# Sheet2.net
KiCad netlist of a schematic drawn in Altium Designer
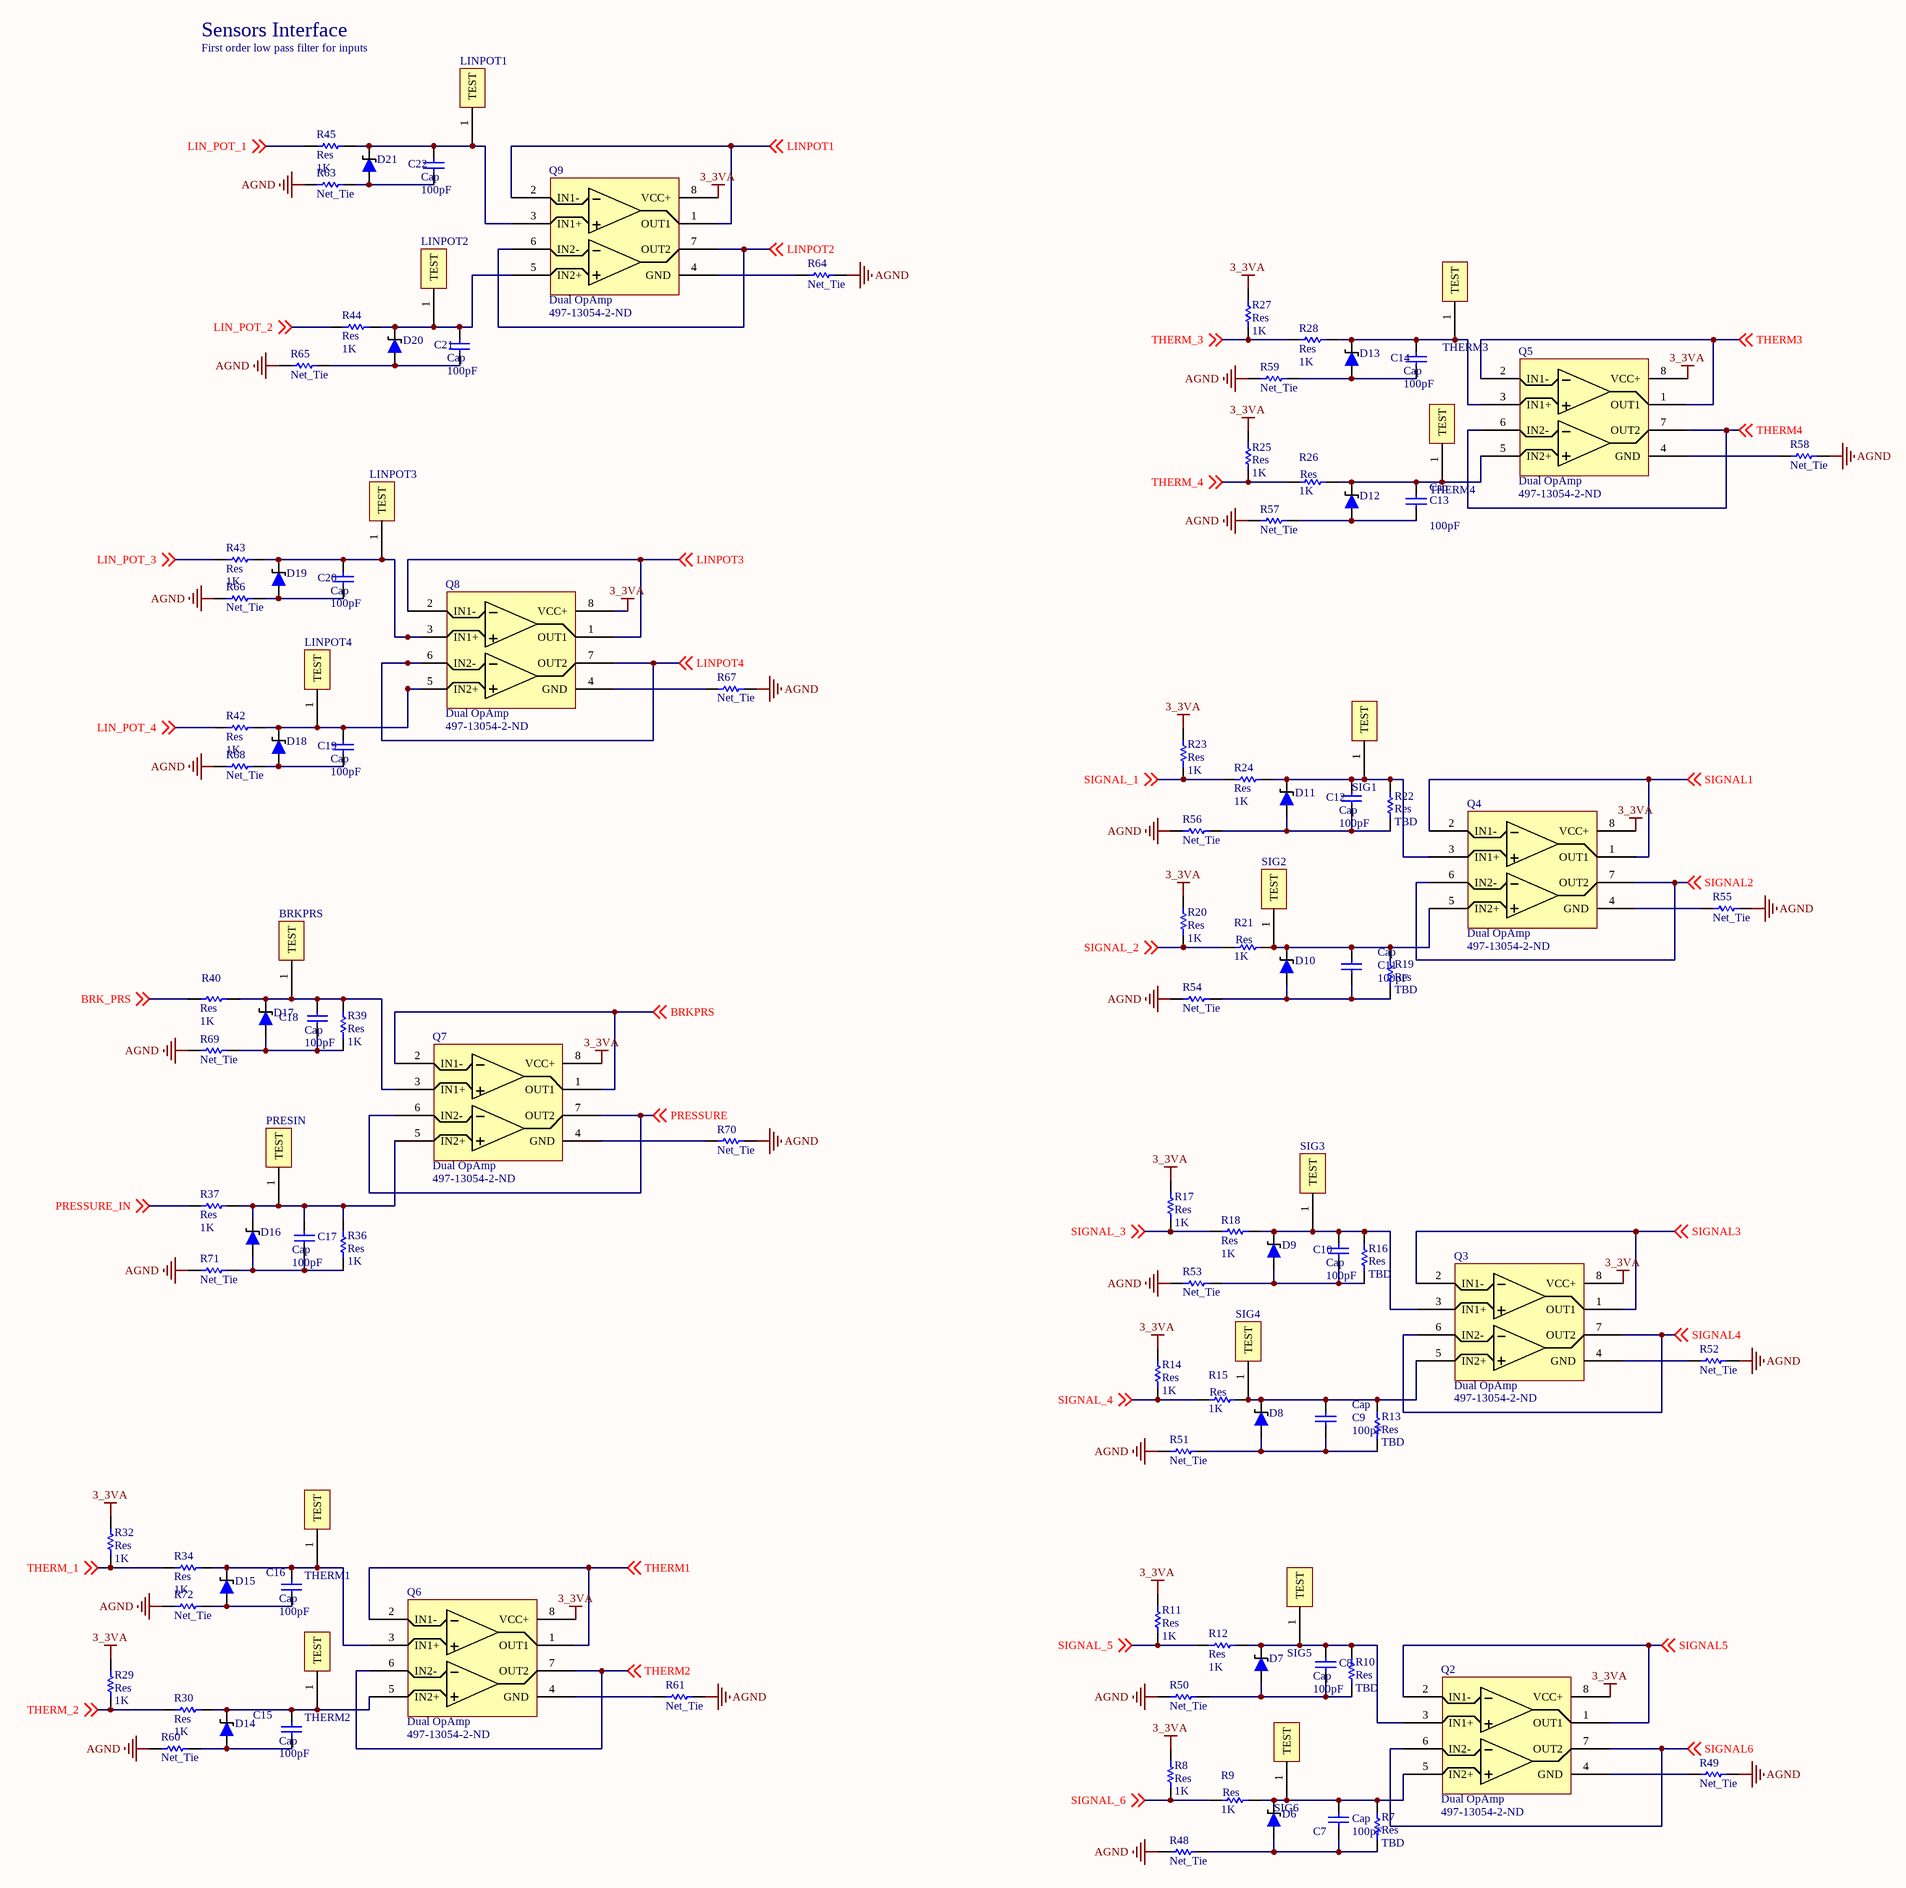
[diagram p0: Sheet2.SchDoc]

(export (version "E")
  (design (tool "Eeschema 10.0.6"))
  (components
    (comp (ref "C7")
      (value "Cap")
      (footprint "C0805")
      (description "Capacitor")
      (fields (field (name "ALTIUM_VALUE") "100pF") (field (name "PUBLISHER") "Altium Limited"))
      (libsource (lib "Capacitors") (part "Cap"))
    )
    (comp (ref "C8")
      (value "Cap")
      (footprint "C0805")
      (description "Capacitor")
      (fields (field (name "ALTIUM_VALUE") "100pF") (field (name "PUBLISHER") "Altium Limited"))
      (libsource (lib "Capacitors") (part "Cap"))
    )
    (comp (ref "C9")
      (value "Cap")
      (footprint "C0805")
      (description "Capacitor")
      (fields (field (name "ALTIUM_VALUE") "100pF") (field (name "PUBLISHER") "Altium Limited"))
      (libsource (lib "Capacitors") (part "Cap"))
    )
    (comp (ref "C10")
      (value "Cap")
      (footprint "C0805")
      (description "Capacitor")
      (fields (field (name "ALTIUM_VALUE") "100pF") (field (name "PUBLISHER") "Altium Limited"))
      (libsource (lib "Capacitors") (part "Cap"))
    )
    (comp (ref "C11")
      (value "Cap")
      (footprint "C0805")
      (description "Capacitor")
      (fields (field (name "ALTIUM_VALUE") "100pF") (field (name "PUBLISHER") "Altium Limited"))
      (libsource (lib "Capacitors") (part "Cap"))
    )
    (comp (ref "C12")
      (value "Cap")
      (footprint "C0805")
      (description "Capacitor")
      (fields (field (name "ALTIUM_VALUE") "100pF") (field (name "PUBLISHER") "Altium Limited"))
      (libsource (lib "Capacitors") (part "Cap"))
    )
    (comp (ref "C13")
      (value "Cap")
      (footprint "C0805")
      (description "Capacitor")
      (fields (field (name "ALTIUM_VALUE") "100pF") (field (name "PUBLISHER") "Altium Limited"))
      (libsource (lib "Capacitors") (part "Cap"))
    )
    (comp (ref "C14")
      (value "Cap")
      (footprint "C0805")
      (description "Capacitor")
      (fields (field (name "ALTIUM_VALUE") "100pF") (field (name "PUBLISHER") "Altium Limited"))
      (libsource (lib "Capacitors") (part "Cap"))
    )
    (comp (ref "C15")
      (value "Cap")
      (footprint "C0805")
      (description "Capacitor")
      (fields (field (name "ALTIUM_VALUE") "100pF") (field (name "PUBLISHER") "Altium Limited"))
      (libsource (lib "Capacitors") (part "Cap"))
    )
    (comp (ref "C16")
      (value "Cap")
      (footprint "C0805")
      (description "Capacitor")
      (fields (field (name "ALTIUM_VALUE") "100pF") (field (name "PUBLISHER") "Altium Limited"))
      (libsource (lib "Capacitors") (part "Cap"))
    )
    (comp (ref "C17")
      (value "Cap")
      (footprint "C0805")
      (description "Capacitor")
      (fields (field (name "ALTIUM_VALUE") "100pF") (field (name "PUBLISHER") "Altium Limited"))
      (libsource (lib "Capacitors") (part "Cap"))
    )
    (comp (ref "C18")
      (value "Cap")
      (footprint "C0805")
      (description "Capacitor")
      (fields (field (name "ALTIUM_VALUE") "100pF") (field (name "PUBLISHER") "Altium Limited"))
      (libsource (lib "Capacitors") (part "Cap"))
    )
    (comp (ref "C19")
      (value "Cap")
      (footprint "C0805")
      (description "Capacitor")
      (fields (field (name "ALTIUM_VALUE") "100pF") (field (name "PUBLISHER") "Altium Limited"))
      (libsource (lib "Capacitors") (part "Cap"))
    )
    (comp (ref "C20")
      (value "Cap")
      (footprint "C0805")
      (description "Capacitor")
      (fields (field (name "ALTIUM_VALUE") "100pF") (field (name "PUBLISHER") "Altium Limited"))
      (libsource (lib "Capacitors") (part "Cap"))
    )
    (comp (ref "C21")
      (value "Cap")
      (footprint "C0805")
      (description "Capacitor")
      (fields (field (name "ALTIUM_VALUE") "100pF") (field (name "PUBLISHER") "Altium Limited"))
      (libsource (lib "Capacitors") (part "Cap"))
    )
    (comp (ref "C22")
      (value "Cap")
      (footprint "C0805")
      (description "Capacitor")
      (fields (field (name "ALTIUM_VALUE") "100pF") (field (name "PUBLISHER") "Altium Limited"))
      (libsource (lib "Capacitors") (part "Cap"))
    )
    (comp (ref "D6")
      (value "MMSZ4684-TP")
      (footprint "MMSZ4684/9")
      (description "Zener Diode 3.3")
      (libsource (lib "DAU_Integrated_Library") (part "MMSZ4684-TP"))
    )
    (comp (ref "D7")
      (value "MMSZ4684-TP")
      (footprint "MMSZ4684/9")
      (description "Zener Diode 3.3")
      (libsource (lib "DAU_Integrated_Library") (part "MMSZ4684-TP"))
    )
    (comp (ref "D8")
      (value "MMSZ4684-TP")
      (footprint "MMSZ4684/9")
      (description "Zener Diode 3.3")
      (libsource (lib "DAU_Integrated_Library") (part "MMSZ4684-TP"))
    )
    (comp (ref "D9")
      (value "MMSZ4684-TP")
      (footprint "MMSZ4684/9")
      (description "Zener Diode 3.3")
      (libsource (lib "DAU_Integrated_Library") (part "MMSZ4684-TP"))
    )
    (comp (ref "D10")
      (value "MMSZ4684-TP")
      (footprint "MMSZ4684/9")
      (description "Zener Diode 3.3")
      (libsource (lib "DAU_Integrated_Library") (part "MMSZ4684-TP"))
    )
    (comp (ref "D11")
      (value "MMSZ4684-TP")
      (footprint "MMSZ4684/9")
      (description "Zener Diode 3.3")
      (libsource (lib "DAU_Integrated_Library") (part "MMSZ4684-TP"))
    )
    (comp (ref "D12")
      (value "MMSZ4684-TP")
      (footprint "MMSZ4684/9")
      (description "Zener Diode 3.3")
      (libsource (lib "DAU_Integrated_Library") (part "MMSZ4684-TP"))
    )
    (comp (ref "D13")
      (value "MMSZ4684-TP")
      (footprint "MMSZ4684/9")
      (description "Zener Diode 3.3")
      (libsource (lib "DAU_Integrated_Library") (part "MMSZ4684-TP"))
    )
    (comp (ref "D14")
      (value "MMSZ4684-TP")
      (footprint "MMSZ4684/9")
      (description "Zener Diode 3.3")
      (libsource (lib "DAU_Integrated_Library") (part "MMSZ4684-TP"))
    )
    (comp (ref "D15")
      (value "MMSZ4684-TP")
      (footprint "MMSZ4684/9")
      (description "Zener Diode 3.3")
      (libsource (lib "DAU_Integrated_Library") (part "MMSZ4684-TP"))
    )
    (comp (ref "D16")
      (value "MMSZ4689-TP")
      (footprint "MMSZ4684/9")
      (description "Zener Diode 5.1")
      (libsource (lib "DAU_Integrated_Library") (part "MMSZ4689-TP"))
    )
    (comp (ref "D17")
      (value "MMSZ4689-TP")
      (footprint "MMSZ4684/9")
      (description "Zener Diode 5.1")
      (libsource (lib "DAU_Integrated_Library") (part "MMSZ4689-TP"))
    )
    (comp (ref "D18")
      (value "MMSZ4684-TP")
      (footprint "MMSZ4684/9")
      (description "Zener Diode 3.3")
      (libsource (lib "DAU_Integrated_Library") (part "MMSZ4684-TP"))
    )
    (comp (ref "D19")
      (value "MMSZ4684-TP")
      (footprint "MMSZ4684/9")
      (description "Zener Diode 3.3")
      (libsource (lib "DAU_Integrated_Library") (part "MMSZ4684-TP"))
    )
    (comp (ref "D20")
      (value "MMSZ4684-TP")
      (footprint "MMSZ4684/9")
      (description "Zener Diode 3.3")
      (libsource (lib "DAU_Integrated_Library") (part "MMSZ4684-TP"))
    )
    (comp (ref "D21")
      (value "MMSZ4684-TP")
      (footprint "MMSZ4684/9")
      (description "Zener Diode 3.3")
      (libsource (lib "DAU_Integrated_Library") (part "MMSZ4684-TP"))
    )
    (comp (ref "Q2")
      (value "Dual OpAmp")
      (footprint "LMV358LIDT")
      (description "Standard Dual OpAmp")
      (fields (field (name "SUPPLIER PART NUMBER 1") "497-13054-2-ND"))
      (libsource (lib "DAU_Integrated_Library") (part "LMV358LIDT"))
    )
    (comp (ref "Q3")
      (value "Dual OpAmp")
      (footprint "LMV358LIDT")
      (description "Standard Dual OpAmp")
      (fields (field (name "SUPPLIER PART NUMBER 1") "497-13054-2-ND"))
      (libsource (lib "DAU_Integrated_Library") (part "LMV358LIDT"))
    )
    (comp (ref "Q4")
      (value "Dual OpAmp")
      (footprint "LMV358LIDT")
      (description "Standard Dual OpAmp")
      (fields (field (name "SUPPLIER PART NUMBER 1") "497-13054-2-ND"))
      (libsource (lib "DAU_Integrated_Library") (part "LMV358LIDT"))
    )
    (comp (ref "Q5")
      (value "Dual OpAmp")
      (footprint "LMV358LIDT")
      (description "Standard Dual OpAmp")
      (fields (field (name "SUPPLIER PART NUMBER 1") "497-13054-2-ND"))
      (libsource (lib "DAU_Integrated_Library") (part "LMV358LIDT"))
    )
    (comp (ref "Q6")
      (value "Dual OpAmp")
      (footprint "LMV358LIDT")
      (description "Standard Dual OpAmp")
      (fields (field (name "SUPPLIER PART NUMBER 1") "497-13054-2-ND"))
      (libsource (lib "DAU_Integrated_Library") (part "LMV358LIDT"))
    )
    (comp (ref "Q7")
      (value "Dual OpAmp")
      (footprint "LMV358LIDT")
      (description "Standard Dual OpAmp")
      (fields (field (name "SUPPLIER PART NUMBER 1") "497-13054-2-ND"))
      (libsource (lib "DAU_Integrated_Library") (part "LMV358LIDT"))
    )
    (comp (ref "Q8")
      (value "Dual OpAmp")
      (footprint "LMV358LIDT")
      (description "Standard Dual OpAmp")
      (fields (field (name "SUPPLIER PART NUMBER 1") "497-13054-2-ND"))
      (libsource (lib "DAU_Integrated_Library") (part "LMV358LIDT"))
    )
    (comp (ref "Q9")
      (value "Dual OpAmp")
      (footprint "LMV358LIDT")
      (description "Standard Dual OpAmp")
      (fields (field (name "SUPPLIER PART NUMBER 1") "497-13054-2-ND"))
      (libsource (lib "DAU_Integrated_Library") (part "LMV358LIDT"))
    )
    (comp (ref "R7")
      (value "Res")
      (footprint "2012[0805]")
      (description "Surface Mount Resistor")
      (fields (field (name "ALTIUM_VALUE") "TBD") (field (name "PUBLISHER") "Altium Limited"))
      (libsource (lib "Resistors") (part "Res"))
    )
    (comp (ref "R8")
      (value "Res")
      (footprint "2012[0805]")
      (description "Surface Mount Resistor")
      (fields (field (name "ALTIUM_VALUE") "1K") (field (name "PUBLISHER") "Altium Limited"))
      (libsource (lib "Resistors") (part "Res"))
    )
    (comp (ref "R9")
      (value "Res")
      (footprint "2012[0805]")
      (description "Surface Mount Resistor")
      (fields (field (name "ALTIUM_VALUE") "1K") (field (name "PUBLISHER") "Altium Limited"))
      (libsource (lib "Resistors") (part "Res"))
    )
    (comp (ref "R10")
      (value "Res")
      (footprint "2012[0805]")
      (description "Surface Mount Resistor")
      (fields (field (name "ALTIUM_VALUE") "TBD") (field (name "PUBLISHER") "Altium Limited"))
      (libsource (lib "Resistors") (part "Res"))
    )
    (comp (ref "R11")
      (value "Res")
      (footprint "2012[0805]")
      (description "Surface Mount Resistor")
      (fields (field (name "ALTIUM_VALUE") "1K") (field (name "PUBLISHER") "Altium Limited"))
      (libsource (lib "Resistors") (part "Res"))
    )
    (comp (ref "R12")
      (value "Res")
      (footprint "2012[0805]")
      (description "Surface Mount Resistor")
      (fields (field (name "ALTIUM_VALUE") "1K") (field (name "PUBLISHER") "Altium Limited"))
      (libsource (lib "Resistors") (part "Res"))
    )
    (comp (ref "R13")
      (value "Res")
      (footprint "2012[0805]")
      (description "Surface Mount Resistor")
      (fields (field (name "ALTIUM_VALUE") "TBD") (field (name "PUBLISHER") "Altium Limited"))
      (libsource (lib "Resistors") (part "Res"))
    )
    (comp (ref "R14")
      (value "Res")
      (footprint "2012[0805]")
      (description "Surface Mount Resistor")
      (fields (field (name "ALTIUM_VALUE") "1K") (field (name "PUBLISHER") "Altium Limited"))
      (libsource (lib "Resistors") (part "Res"))
    )
    (comp (ref "R15")
      (value "Res")
      (footprint "2012[0805]")
      (description "Surface Mount Resistor")
      (fields (field (name "ALTIUM_VALUE") "1K") (field (name "PUBLISHER") "Altium Limited"))
      (libsource (lib "Resistors") (part "Res"))
    )
    (comp (ref "R16")
      (value "Res")
      (footprint "2012[0805]")
      (description "Surface Mount Resistor")
      (fields (field (name "ALTIUM_VALUE") "TBD") (field (name "PUBLISHER") "Altium Limited"))
      (libsource (lib "Resistors") (part "Res"))
    )
    (comp (ref "R17")
      (value "Res")
      (footprint "2012[0805]")
      (description "Surface Mount Resistor")
      (fields (field (name "ALTIUM_VALUE") "1K") (field (name "PUBLISHER") "Altium Limited"))
      (libsource (lib "Resistors") (part "Res"))
    )
    (comp (ref "R18")
      (value "Res")
      (footprint "2012[0805]")
      (description "Surface Mount Resistor")
      (fields (field (name "ALTIUM_VALUE") "1K") (field (name "PUBLISHER") "Altium Limited"))
      (libsource (lib "Resistors") (part "Res"))
    )
    (comp (ref "R19")
      (value "Res")
      (footprint "2012[0805]")
      (description "Surface Mount Resistor")
      (fields (field (name "ALTIUM_VALUE") "TBD") (field (name "PUBLISHER") "Altium Limited"))
      (libsource (lib "Resistors") (part "Res"))
    )
    (comp (ref "R20")
      (value "Res")
      (footprint "2012[0805]")
      (description "Surface Mount Resistor")
      (fields (field (name "ALTIUM_VALUE") "1K") (field (name "PUBLISHER") "Altium Limited"))
      (libsource (lib "Resistors") (part "Res"))
    )
    (comp (ref "R21")
      (value "Res")
      (footprint "2012[0805]")
      (description "Surface Mount Resistor")
      (fields (field (name "ALTIUM_VALUE") "1K") (field (name "PUBLISHER") "Altium Limited"))
      (libsource (lib "Resistors") (part "Res"))
    )
    (comp (ref "R22")
      (value "Res")
      (footprint "2012[0805]")
      (description "Surface Mount Resistor")
      (fields (field (name "ALTIUM_VALUE") "TBD") (field (name "PUBLISHER") "Altium Limited"))
      (libsource (lib "Resistors") (part "Res"))
    )
    (comp (ref "R23")
      (value "Res")
      (footprint "2012[0805]")
      (description "Surface Mount Resistor")
      (fields (field (name "ALTIUM_VALUE") "1K") (field (name "PUBLISHER") "Altium Limited"))
      (libsource (lib "Resistors") (part "Res"))
    )
    (comp (ref "R24")
      (value "Res")
      (footprint "2012[0805]")
      (description "Surface Mount Resistor")
      (fields (field (name "ALTIUM_VALUE") "1K") (field (name "PUBLISHER") "Altium Limited"))
      (libsource (lib "Resistors") (part "Res"))
    )
    (comp (ref "R25")
      (value "Res")
      (footprint "2012[0805]")
      (description "Surface Mount Resistor")
      (fields (field (name "ALTIUM_VALUE") "1K") (field (name "PUBLISHER") "Altium Limited"))
      (libsource (lib "Resistors") (part "Res"))
    )
    (comp (ref "R26")
      (value "Res")
      (footprint "2012[0805]")
      (description "Surface Mount Resistor")
      (fields (field (name "ALTIUM_VALUE") "1K") (field (name "PUBLISHER") "Altium Limited"))
      (libsource (lib "Resistors") (part "Res"))
    )
    (comp (ref "R27")
      (value "Res")
      (footprint "2012[0805]")
      (description "Surface Mount Resistor")
      (fields (field (name "ALTIUM_VALUE") "1K") (field (name "PUBLISHER") "Altium Limited"))
      (libsource (lib "Resistors") (part "Res"))
    )
    (comp (ref "R28")
      (value "Res")
      (footprint "2012[0805]")
      (description "Surface Mount Resistor")
      (fields (field (name "ALTIUM_VALUE") "1K") (field (name "PUBLISHER") "Altium Limited"))
      (libsource (lib "Resistors") (part "Res"))
    )
    (comp (ref "R29")
      (value "Res")
      (footprint "2012[0805]")
      (description "Surface Mount Resistor")
      (fields (field (name "ALTIUM_VALUE") "1K") (field (name "PUBLISHER") "Altium Limited"))
      (libsource (lib "Resistors") (part "Res"))
    )
    (comp (ref "R30")
      (value "Res")
      (footprint "2012[0805]")
      (description "Surface Mount Resistor")
      (fields (field (name "ALTIUM_VALUE") "1K") (field (name "PUBLISHER") "Altium Limited"))
      (libsource (lib "Resistors") (part "Res"))
    )
    (comp (ref "R32")
      (value "Res")
      (footprint "2012[0805]")
      (description "Surface Mount Resistor")
      (fields (field (name "ALTIUM_VALUE") "1K") (field (name "PUBLISHER") "Altium Limited"))
      (libsource (lib "Resistors") (part "Res"))
    )
    (comp (ref "R34")
      (value "Res")
      (footprint "2012[0805]")
      (description "Surface Mount Resistor")
      (fields (field (name "ALTIUM_VALUE") "1K") (field (name "PUBLISHER") "Altium Limited"))
      (libsource (lib "Resistors") (part "Res"))
    )
    (comp (ref "R36")
      (value "Res")
      (footprint "2012[0805]")
      (description "Surface Mount Resistor")
      (fields (field (name "ALTIUM_VALUE") "1K") (field (name "PUBLISHER") "Altium Limited"))
      (libsource (lib "Resistors") (part "Res"))
    )
    (comp (ref "R37")
      (value "Res")
      (footprint "2012[0805]")
      (description "Surface Mount Resistor")
      (fields (field (name "ALTIUM_VALUE") "1K") (field (name "PUBLISHER") "Altium Limited"))
      (libsource (lib "Resistors") (part "Res"))
    )
    (comp (ref "R39")
      (value "Res")
      (footprint "2012[0805]")
      (description "Surface Mount Resistor")
      (fields (field (name "ALTIUM_VALUE") "1K") (field (name "PUBLISHER") "Altium Limited"))
      (libsource (lib "Resistors") (part "Res"))
    )
    (comp (ref "R40")
      (value "Res")
      (footprint "2012[0805]")
      (description "Surface Mount Resistor")
      (fields (field (name "ALTIUM_VALUE") "1K") (field (name "PUBLISHER") "Altium Limited"))
      (libsource (lib "Resistors") (part "Res"))
    )
    (comp (ref "R42")
      (value "Res")
      (footprint "2012[0805]")
      (description "Surface Mount Resistor")
      (fields (field (name "ALTIUM_VALUE") "1K") (field (name "PUBLISHER") "Altium Limited"))
      (libsource (lib "Resistors") (part "Res"))
    )
    (comp (ref "R43")
      (value "Res")
      (footprint "2012[0805]")
      (description "Surface Mount Resistor")
      (fields (field (name "ALTIUM_VALUE") "1K") (field (name "PUBLISHER") "Altium Limited"))
      (libsource (lib "Resistors") (part "Res"))
    )
    (comp (ref "R44")
      (value "Res")
      (footprint "2012[0805]")
      (description "Surface Mount Resistor")
      (fields (field (name "ALTIUM_VALUE") "1K") (field (name "PUBLISHER") "Altium Limited"))
      (libsource (lib "Resistors") (part "Res"))
    )
    (comp (ref "R45")
      (value "Res")
      (footprint "2012[0805]")
      (description "Surface Mount Resistor")
      (fields (field (name "ALTIUM_VALUE") "1K") (field (name "PUBLISHER") "Altium Limited"))
      (libsource (lib "Resistors") (part "Res"))
    )
    (comp (ref "R48")
      (value "Net_Tie")
      (footprint "NetTie 0805 10mil")
      (description "Surface Mount Resistor")
      (libsource (lib "Resistors") (part "Res_NetTie"))
    )
    (comp (ref "R49")
      (value "Net_Tie")
      (footprint "NetTie 0805 10mil")
      (description "Surface Mount Resistor")
      (libsource (lib "Resistors") (part "Res_NetTie"))
    )
    (comp (ref "R50")
      (value "Net_Tie")
      (footprint "NetTie 0805 10mil")
      (description "Surface Mount Resistor")
      (libsource (lib "Resistors") (part "Res_NetTie"))
    )
    (comp (ref "R51")
      (value "Net_Tie")
      (footprint "NetTie 0805 10mil")
      (description "Surface Mount Resistor")
      (libsource (lib "Resistors") (part "Res_NetTie"))
    )
    (comp (ref "R52")
      (value "Net_Tie")
      (footprint "NetTie 0805 10mil")
      (description "Surface Mount Resistor")
      (libsource (lib "Resistors") (part "Res_NetTie"))
    )
    (comp (ref "R53")
      (value "Net_Tie")
      (footprint "NetTie 0805 10mil")
      (description "Surface Mount Resistor")
      (libsource (lib "Resistors") (part "Res_NetTie"))
    )
    (comp (ref "R54")
      (value "Net_Tie")
      (footprint "NetTie 0805 10mil")
      (description "Surface Mount Resistor")
      (libsource (lib "Resistors") (part "Res_NetTie"))
    )
    (comp (ref "R55")
      (value "Net_Tie")
      (footprint "NetTie 0805 10mil")
      (description "Surface Mount Resistor")
      (libsource (lib "Resistors") (part "Res_NetTie"))
    )
    (comp (ref "R56")
      (value "Net_Tie")
      (footprint "NetTie 0805 10mil")
      (description "Surface Mount Resistor")
      (libsource (lib "Resistors") (part "Res_NetTie"))
    )
    (comp (ref "R57")
      (value "Net_Tie")
      (footprint "NetTie 0805 10mil")
      (description "Surface Mount Resistor")
      (libsource (lib "Resistors") (part "Res_NetTie"))
    )
    (comp (ref "R58")
      (value "Net_Tie")
      (footprint "NetTie 0805 10mil")
      (description "Surface Mount Resistor")
      (libsource (lib "Resistors") (part "Res_NetTie"))
    )
    (comp (ref "R59")
      (value "Net_Tie")
      (footprint "NetTie 0805 10mil")
      (description "Surface Mount Resistor")
      (libsource (lib "Resistors") (part "Res_NetTie"))
    )
    (comp (ref "R60")
      (value "Net_Tie")
      (footprint "NetTie 0805 10mil")
      (description "Surface Mount Resistor")
      (libsource (lib "Resistors") (part "Res_NetTie"))
    )
    (comp (ref "R61")
      (value "Net_Tie")
      (footprint "NetTie 0805 10mil")
      (description "Surface Mount Resistor")
      (libsource (lib "Resistors") (part "Res_NetTie"))
    )
    (comp (ref "R63")
      (value "Net_Tie")
      (footprint "NetTie 0805 10mil")
      (description "Surface Mount Resistor")
      (libsource (lib "Resistors") (part "Res_NetTie"))
    )
    (comp (ref "R64")
      (value "Net_Tie")
      (footprint "NetTie 0805 10mil")
      (description "Surface Mount Resistor")
      (libsource (lib "Resistors") (part "Res_NetTie"))
    )
    (comp (ref "R65")
      (value "Net_Tie")
      (footprint "NetTie 0805 10mil")
      (description "Surface Mount Resistor")
      (libsource (lib "Resistors") (part "Res_NetTie"))
    )
    (comp (ref "R66")
      (value "Net_Tie")
      (footprint "NetTie 0805 10mil")
      (description "Surface Mount Resistor")
      (libsource (lib "Resistors") (part "Res_NetTie"))
    )
    (comp (ref "R67")
      (value "Net_Tie")
      (footprint "NetTie 0805 10mil")
      (description "Surface Mount Resistor")
      (libsource (lib "Resistors") (part "Res_NetTie"))
    )
    (comp (ref "R68")
      (value "Net_Tie")
      (footprint "NetTie 0805 10mil")
      (description "Surface Mount Resistor")
      (libsource (lib "Resistors") (part "Res_NetTie"))
    )
    (comp (ref "R69")
      (value "Net_Tie")
      (footprint "NetTie 0805 10mil")
      (description "Surface Mount Resistor")
      (libsource (lib "Resistors") (part "Res_NetTie"))
    )
    (comp (ref "R70")
      (value "Net_Tie")
      (footprint "NetTie 0805 10mil")
      (description "Surface Mount Resistor")
      (libsource (lib "Resistors") (part "Res_NetTie"))
    )
    (comp (ref "R71")
      (value "Net_Tie")
      (footprint "NetTie 0805 10mil")
      (description "Surface Mount Resistor")
      (libsource (lib "Resistors") (part "Res_NetTie"))
    )
    (comp (ref "R72")
      (value "Net_Tie")
      (footprint "NetTie 0805 10mil")
      (description "Surface Mount Resistor")
      (libsource (lib "Resistors") (part "Res_NetTie"))
    )
    (comp (ref "TP1")
      (value "SIG6")
      (footprint "TEST POINT 5000K")
      (description "5000-5004, 5015-5019 Keystone Electronics")
      (libsource (lib "Mechanical_Devices") (part "Test Point"))
    )
    (comp (ref "TP2")
      (value "SIG5")
      (footprint "TEST POINT 5000K")
      (description "5000-5004, 5015-5019 Keystone Electronics")
      (libsource (lib "Mechanical_Devices") (part "Test Point"))
    )
    (comp (ref "TP3")
      (value "SIG4")
      (footprint "TEST POINT 5000K")
      (description "5000-5004, 5015-5019 Keystone Electronics")
      (libsource (lib "Mechanical_Devices") (part "Test Point"))
    )
    (comp (ref "TP4")
      (value "SIG3")
      (footprint "TEST POINT 5000K")
      (description "5000-5004, 5015-5019 Keystone Electronics")
      (libsource (lib "Mechanical_Devices") (part "Test Point"))
    )
    (comp (ref "TP5")
      (value "SIG2")
      (footprint "TEST POINT 5000K")
      (description "5000-5004, 5015-5019 Keystone Electronics")
      (libsource (lib "Mechanical_Devices") (part "Test Point"))
    )
    (comp (ref "TP6")
      (value "SIG1")
      (footprint "TEST POINT 5000K")
      (description "5000-5004, 5015-5019 Keystone Electronics")
      (libsource (lib "Mechanical_Devices") (part "Test Point"))
    )
    (comp (ref "TP7")
      (value "THERM4")
      (footprint "TEST POINT 5000K")
      (description "5000-5004, 5015-5019 Keystone Electronics")
      (libsource (lib "Mechanical_Devices") (part "Test Point"))
    )
    (comp (ref "TP8")
      (value "THERM3")
      (footprint "TEST POINT 5000K")
      (description "5000-5004, 5015-5019 Keystone Electronics")
      (libsource (lib "Mechanical_Devices") (part "Test Point"))
    )
    (comp (ref "TP9")
      (value "THERM2")
      (footprint "TEST POINT 5000K")
      (description "5000-5004, 5015-5019 Keystone Electronics")
      (libsource (lib "Mechanical_Devices") (part "Test Point"))
    )
    (comp (ref "TP10")
      (value "THERM1")
      (footprint "TEST POINT 5000K")
      (description "5000-5004, 5015-5019 Keystone Electronics")
      (libsource (lib "Mechanical_Devices") (part "Test Point"))
    )
    (comp (ref "TP11")
      (value "PRESIN")
      (footprint "TEST POINT 5000K")
      (description "5000-5004, 5015-5019 Keystone Electronics")
      (libsource (lib "Mechanical_Devices") (part "Test Point"))
    )
    (comp (ref "TP12")
      (value "BRKPRS")
      (footprint "TEST POINT 5000K")
      (description "5000-5004, 5015-5019 Keystone Electronics")
      (libsource (lib "Mechanical_Devices") (part "Test Point"))
    )
    (comp (ref "TP13")
      (value "LINPOT4")
      (footprint "TEST POINT 5000K")
      (description "5000-5004, 5015-5019 Keystone Electronics")
      (libsource (lib "Mechanical_Devices") (part "Test Point"))
    )
    (comp (ref "TP14")
      (value "LINPOT3")
      (footprint "TEST POINT 5000K")
      (description "5000-5004, 5015-5019 Keystone Electronics")
      (libsource (lib "Mechanical_Devices") (part "Test Point"))
    )
    (comp (ref "TP15")
      (value "LINPOT2")
      (footprint "TEST POINT 5000K")
      (description "5000-5004, 5015-5019 Keystone Electronics")
      (libsource (lib "Mechanical_Devices") (part "Test Point"))
    )
    (comp (ref "TP16")
      (value "LINPOT1")
      (footprint "TEST POINT 5000K")
      (description "5000-5004, 5015-5019 Keystone Electronics")
      (libsource (lib "Mechanical_Devices") (part "Test Point"))
    )
  )
  (nets
    (net (code "1") (name "3_3VA") (class "Default")
      (node (ref "Q2") (pin "8") (pinfunction "VCC+_8") (pintype "passive"))
      (node (ref "Q3") (pin "8") (pinfunction "VCC+_8") (pintype "passive"))
      (node (ref "Q4") (pin "8") (pinfunction "VCC+_8") (pintype "passive"))
      (node (ref "Q5") (pin "8") (pinfunction "VCC+_8") (pintype "passive"))
      (node (ref "Q6") (pin "8") (pinfunction "VCC+_8") (pintype "passive"))
      (node (ref "Q7") (pin "8") (pinfunction "VCC+_8") (pintype "passive"))
      (node (ref "Q8") (pin "8") (pinfunction "VCC+_8") (pintype "passive"))
      (node (ref "Q9") (pin "8") (pinfunction "VCC+_8") (pintype "passive"))
      (node (ref "R11") (pin "2") (pinfunction "2_2") (pintype "passive"))
      (node (ref "R14") (pin "2") (pinfunction "2_2") (pintype "passive"))
      (node (ref "R17") (pin "2") (pinfunction "2_2") (pintype "passive"))
      (node (ref "R20") (pin "2") (pinfunction "2_2") (pintype "passive"))
      (node (ref "R23") (pin "2") (pinfunction "2_2") (pintype "passive"))
      (node (ref "R25") (pin "2") (pinfunction "2_2") (pintype "passive"))
      (node (ref "R27") (pin "2") (pinfunction "2_2") (pintype "passive"))
      (node (ref "R29") (pin "2") (pinfunction "2_2") (pintype "passive"))
      (node (ref "R32") (pin "2") (pinfunction "2_2") (pintype "passive"))
      (node (ref "R8") (pin "2") (pinfunction "2_2") (pintype "passive"))
    )
    (net (code "2") (name "AGND") (class "Default")
      (node (ref "R48") (pin "2") (pinfunction "2_2") (pintype "passive"))
      (node (ref "R49") (pin "2") (pinfunction "2_2") (pintype "passive"))
      (node (ref "R50") (pin "2") (pinfunction "2_2") (pintype "passive"))
      (node (ref "R51") (pin "2") (pinfunction "2_2") (pintype "passive"))
      (node (ref "R52") (pin "2") (pinfunction "2_2") (pintype "passive"))
      (node (ref "R53") (pin "2") (pinfunction "2_2") (pintype "passive"))
      (node (ref "R54") (pin "2") (pinfunction "2_2") (pintype "passive"))
      (node (ref "R55") (pin "2") (pinfunction "2_2") (pintype "passive"))
      (node (ref "R56") (pin "2") (pinfunction "2_2") (pintype "passive"))
      (node (ref "R57") (pin "2") (pinfunction "2_2") (pintype "passive"))
      (node (ref "R58") (pin "2") (pinfunction "2_2") (pintype "passive"))
      (node (ref "R59") (pin "2") (pinfunction "2_2") (pintype "passive"))
      (node (ref "R60") (pin "2") (pinfunction "2_2") (pintype "passive"))
      (node (ref "R61") (pin "2") (pinfunction "2_2") (pintype "passive"))
      (node (ref "R63") (pin "1") (pinfunction "1_1") (pintype "passive"))
      (node (ref "R64") (pin "2") (pinfunction "2_2") (pintype "passive"))
      (node (ref "R65") (pin "1") (pinfunction "1_1") (pintype "passive"))
      (node (ref "R66") (pin "2") (pinfunction "2_2") (pintype "passive"))
      (node (ref "R67") (pin "2") (pinfunction "2_2") (pintype "passive"))
      (node (ref "R68") (pin "2") (pinfunction "2_2") (pintype "passive"))
      (node (ref "R69") (pin "2") (pinfunction "2_2") (pintype "passive"))
      (node (ref "R70") (pin "2") (pinfunction "2_2") (pintype "passive"))
      (node (ref "R71") (pin "2") (pinfunction "2_2") (pintype "passive"))
      (node (ref "R72") (pin "2") (pinfunction "2_2") (pintype "passive"))
    )
    (net (code "3") (name "BRKPRS") (class "Default")
      (node (ref "Q7") (pin "1") (pinfunction "OUT1_1") (pintype "passive"))
      (node (ref "Q7") (pin "2") (pinfunction "IN1-_2") (pintype "passive"))
    )
    (net (code "4") (name "BRK_PRS") (class "Default")
      (node (ref "R40") (pin "1") (pinfunction "1_1") (pintype "passive"))
    )
    (net (code "5") (name "LINPOT1") (class "Default")
      (node (ref "Q9") (pin "1") (pinfunction "OUT1_1") (pintype "passive"))
      (node (ref "Q9") (pin "2") (pinfunction "IN1-_2") (pintype "passive"))
    )
    (net (code "6") (name "LINPOT2") (class "Default")
      (node (ref "Q9") (pin "6") (pinfunction "IN2-_6") (pintype "passive"))
      (node (ref "Q9") (pin "7") (pinfunction "OUT2_7") (pintype "passive"))
    )
    (net (code "7") (name "LINPOT3") (class "Default")
      (node (ref "Q8") (pin "1") (pinfunction "OUT1_1") (pintype "passive"))
      (node (ref "Q8") (pin "2") (pinfunction "IN1-_2") (pintype "passive"))
    )
    (net (code "8") (name "LINPOT4") (class "Default")
      (node (ref "Q8") (pin "6") (pinfunction "IN2-_6") (pintype "passive"))
      (node (ref "Q8") (pin "7") (pinfunction "OUT2_7") (pintype "passive"))
    )
    (net (code "9") (name "LIN_POT_1") (class "Default")
      (node (ref "R45") (pin "1") (pinfunction "1_1") (pintype "passive"))
    )
    (net (code "10") (name "LIN_POT_2") (class "Default")
      (node (ref "R44") (pin "1") (pinfunction "1_1") (pintype "passive"))
    )
    (net (code "11") (name "LIN_POT_3") (class "Default")
      (node (ref "R43") (pin "1") (pinfunction "1_1") (pintype "passive"))
    )
    (net (code "12") (name "LIN_POT_4") (class "Default")
      (node (ref "R42") (pin "1") (pinfunction "1_1") (pintype "passive"))
    )
    (net (code "13") (name "Net-(C7-Pad1)") (class "Default")
      (node (ref "C7") (pin "1") (pinfunction "1_1") (pintype "passive"))
      (node (ref "D6") (pin "1") (pintype "passive"))
      (node (ref "R48") (pin "1") (pinfunction "1_1") (pintype "passive"))
      (node (ref "R7") (pin "2") (pinfunction "2_2") (pintype "passive"))
    )
    (net (code "14") (name "Net-(C8-Pad1)") (class "Default")
      (node (ref "C8") (pin "1") (pinfunction "1_1") (pintype "passive"))
      (node (ref "D7") (pin "1") (pintype "passive"))
      (node (ref "R10") (pin "2") (pinfunction "2_2") (pintype "passive"))
      (node (ref "R50") (pin "1") (pinfunction "1_1") (pintype "passive"))
    )
    (net (code "15") (name "Net-(C9-Pad1)") (class "Default")
      (node (ref "C9") (pin "1") (pinfunction "1_1") (pintype "passive"))
      (node (ref "D8") (pin "1") (pintype "passive"))
      (node (ref "R13") (pin "2") (pinfunction "2_2") (pintype "passive"))
      (node (ref "R51") (pin "1") (pinfunction "1_1") (pintype "passive"))
    )
    (net (code "16") (name "Net-(C10-Pad1)") (class "Default")
      (node (ref "C10") (pin "1") (pinfunction "1_1") (pintype "passive"))
      (node (ref "D9") (pin "1") (pintype "passive"))
      (node (ref "R16") (pin "2") (pinfunction "2_2") (pintype "passive"))
      (node (ref "R53") (pin "1") (pinfunction "1_1") (pintype "passive"))
    )
    (net (code "17") (name "Net-(C11-Pad1)") (class "Default")
      (node (ref "C11") (pin "1") (pinfunction "1_1") (pintype "passive"))
      (node (ref "D10") (pin "1") (pintype "passive"))
      (node (ref "R19") (pin "2") (pinfunction "2_2") (pintype "passive"))
      (node (ref "R54") (pin "1") (pinfunction "1_1") (pintype "passive"))
    )
    (net (code "18") (name "Net-(C12-Pad1)") (class "Default")
      (node (ref "C12") (pin "1") (pinfunction "1_1") (pintype "passive"))
      (node (ref "D11") (pin "1") (pintype "passive"))
      (node (ref "R22") (pin "2") (pinfunction "2_2") (pintype "passive"))
      (node (ref "R56") (pin "1") (pinfunction "1_1") (pintype "passive"))
    )
    (net (code "19") (name "Net-(C13-Pad1)") (class "Default")
      (node (ref "C13") (pin "1") (pinfunction "1_1") (pintype "passive"))
      (node (ref "D12") (pin "1") (pintype "passive"))
      (node (ref "R57") (pin "1") (pinfunction "1_1") (pintype "passive"))
    )
    (net (code "20") (name "Net-(C14-Pad1)") (class "Default")
      (node (ref "C14") (pin "1") (pinfunction "1_1") (pintype "passive"))
      (node (ref "D13") (pin "1") (pintype "passive"))
      (node (ref "R59") (pin "1") (pinfunction "1_1") (pintype "passive"))
    )
    (net (code "21") (name "Net-(C15-Pad1)") (class "Default")
      (node (ref "C15") (pin "1") (pinfunction "1_1") (pintype "passive"))
      (node (ref "D14") (pin "1") (pintype "passive"))
      (node (ref "R60") (pin "1") (pinfunction "1_1") (pintype "passive"))
    )
    (net (code "22") (name "Net-(C16-Pad1)") (class "Default")
      (node (ref "C16") (pin "1") (pinfunction "1_1") (pintype "passive"))
      (node (ref "D15") (pin "1") (pintype "passive"))
      (node (ref "R72") (pin "1") (pinfunction "1_1") (pintype "passive"))
    )
    (net (code "23") (name "Net-(C17-Pad1)") (class "Default")
      (node (ref "C17") (pin "1") (pinfunction "1_1") (pintype "passive"))
      (node (ref "D16") (pin "1") (pintype "passive"))
      (node (ref "R36") (pin "1") (pinfunction "1_1") (pintype "passive"))
      (node (ref "R71") (pin "1") (pinfunction "1_1") (pintype "passive"))
    )
    (net (code "24") (name "Net-(C18-Pad1)") (class "Default")
      (node (ref "C18") (pin "1") (pinfunction "1_1") (pintype "passive"))
      (node (ref "D17") (pin "1") (pintype "passive"))
      (node (ref "R39") (pin "1") (pinfunction "1_1") (pintype "passive"))
      (node (ref "R69") (pin "1") (pinfunction "1_1") (pintype "passive"))
    )
    (net (code "25") (name "Net-(C19-Pad1)") (class "Default")
      (node (ref "C19") (pin "1") (pinfunction "1_1") (pintype "passive"))
      (node (ref "D18") (pin "1") (pintype "passive"))
      (node (ref "R68") (pin "1") (pinfunction "1_1") (pintype "passive"))
    )
    (net (code "26") (name "Net-(C20-Pad1)") (class "Default")
      (node (ref "C20") (pin "1") (pinfunction "1_1") (pintype "passive"))
      (node (ref "D19") (pin "1") (pintype "passive"))
      (node (ref "R66") (pin "1") (pinfunction "1_1") (pintype "passive"))
    )
    (net (code "27") (name "Net-(C21-Pad1)") (class "Default")
      (node (ref "C21") (pin "1") (pinfunction "1_1") (pintype "passive"))
      (node (ref "D20") (pin "1") (pintype "passive"))
      (node (ref "R65") (pin "2") (pinfunction "2_2") (pintype "passive"))
    )
    (net (code "28") (name "Net-(C22-Pad1)") (class "Default")
      (node (ref "C22") (pin "1") (pinfunction "1_1") (pintype "passive"))
      (node (ref "D21") (pin "1") (pintype "passive"))
      (node (ref "R63") (pin "2") (pinfunction "2_2") (pintype "passive"))
    )
    (net (code "29") (name "Net-(Q2-GND)") (class "Default")
      (node (ref "Q2") (pin "4") (pinfunction "GND_4") (pintype "passive"))
      (node (ref "R49") (pin "1") (pinfunction "1_1") (pintype "passive"))
    )
    (net (code "30") (name "Net-(Q2-IN1+)") (class "Default")
      (node (ref "C8") (pin "2") (pinfunction "2_2") (pintype "passive"))
      (node (ref "D7") (pin "2") (pintype "passive"))
      (node (ref "Q2") (pin "3") (pinfunction "IN1+_3") (pintype "passive"))
      (node (ref "R10") (pin "1") (pinfunction "1_1") (pintype "passive"))
      (node (ref "R12") (pin "2") (pinfunction "2_2") (pintype "passive"))
      (node (ref "TP2") (pin "1") (pinfunction "TEST_1") (pintype "passive"))
    )
    (net (code "31") (name "Net-(Q2-IN2+)") (class "Default")
      (node (ref "C7") (pin "2") (pinfunction "2_2") (pintype "passive"))
      (node (ref "D6") (pin "2") (pintype "passive"))
      (node (ref "Q2") (pin "5") (pinfunction "IN2+_5") (pintype "passive"))
      (node (ref "R7") (pin "1") (pinfunction "1_1") (pintype "passive"))
      (node (ref "R9") (pin "2") (pinfunction "2_2") (pintype "passive"))
      (node (ref "TP1") (pin "1") (pinfunction "TEST_1") (pintype "passive"))
    )
    (net (code "32") (name "Net-(Q3-GND)") (class "Default")
      (node (ref "Q3") (pin "4") (pinfunction "GND_4") (pintype "passive"))
      (node (ref "R52") (pin "1") (pinfunction "1_1") (pintype "passive"))
    )
    (net (code "33") (name "Net-(Q3-IN1+)") (class "Default")
      (node (ref "C10") (pin "2") (pinfunction "2_2") (pintype "passive"))
      (node (ref "D9") (pin "2") (pintype "passive"))
      (node (ref "Q3") (pin "3") (pinfunction "IN1+_3") (pintype "passive"))
      (node (ref "R16") (pin "1") (pinfunction "1_1") (pintype "passive"))
      (node (ref "R18") (pin "2") (pinfunction "2_2") (pintype "passive"))
      (node (ref "TP4") (pin "1") (pinfunction "TEST_1") (pintype "passive"))
    )
    (net (code "34") (name "Net-(Q3-IN2+)") (class "Default")
      (node (ref "C9") (pin "2") (pinfunction "2_2") (pintype "passive"))
      (node (ref "D8") (pin "2") (pintype "passive"))
      (node (ref "Q3") (pin "5") (pinfunction "IN2+_5") (pintype "passive"))
      (node (ref "R13") (pin "1") (pinfunction "1_1") (pintype "passive"))
      (node (ref "R15") (pin "2") (pinfunction "2_2") (pintype "passive"))
      (node (ref "TP3") (pin "1") (pinfunction "TEST_1") (pintype "passive"))
    )
    (net (code "35") (name "Net-(Q4-GND)") (class "Default")
      (node (ref "Q4") (pin "4") (pinfunction "GND_4") (pintype "passive"))
      (node (ref "R55") (pin "1") (pinfunction "1_1") (pintype "passive"))
    )
    (net (code "36") (name "Net-(Q4-IN1+)") (class "Default")
      (node (ref "C12") (pin "2") (pinfunction "2_2") (pintype "passive"))
      (node (ref "D11") (pin "2") (pintype "passive"))
      (node (ref "Q4") (pin "3") (pinfunction "IN1+_3") (pintype "passive"))
      (node (ref "R22") (pin "1") (pinfunction "1_1") (pintype "passive"))
      (node (ref "R24") (pin "2") (pinfunction "2_2") (pintype "passive"))
      (node (ref "TP6") (pin "1") (pinfunction "TEST_1") (pintype "passive"))
    )
    (net (code "37") (name "Net-(Q4-IN2+)") (class "Default")
      (node (ref "C11") (pin "2") (pinfunction "2_2") (pintype "passive"))
      (node (ref "D10") (pin "2") (pintype "passive"))
      (node (ref "Q4") (pin "5") (pinfunction "IN2+_5") (pintype "passive"))
      (node (ref "R19") (pin "1") (pinfunction "1_1") (pintype "passive"))
      (node (ref "R21") (pin "2") (pinfunction "2_2") (pintype "passive"))
      (node (ref "TP5") (pin "1") (pinfunction "TEST_1") (pintype "passive"))
    )
    (net (code "38") (name "Net-(Q5-GND)") (class "Default")
      (node (ref "Q5") (pin "4") (pinfunction "GND_4") (pintype "passive"))
      (node (ref "R58") (pin "1") (pinfunction "1_1") (pintype "passive"))
    )
    (net (code "39") (name "Net-(Q5-IN1+)") (class "Default")
      (node (ref "C14") (pin "2") (pinfunction "2_2") (pintype "passive"))
      (node (ref "D13") (pin "2") (pintype "passive"))
      (node (ref "Q5") (pin "3") (pinfunction "IN1+_3") (pintype "passive"))
      (node (ref "R28") (pin "2") (pinfunction "2_2") (pintype "passive"))
      (node (ref "TP8") (pin "1") (pinfunction "TEST_1") (pintype "passive"))
    )
    (net (code "40") (name "Net-(Q5-IN2+)") (class "Default")
      (node (ref "C13") (pin "2") (pinfunction "2_2") (pintype "passive"))
      (node (ref "D12") (pin "2") (pintype "passive"))
      (node (ref "Q5") (pin "5") (pinfunction "IN2+_5") (pintype "passive"))
      (node (ref "R26") (pin "2") (pinfunction "2_2") (pintype "passive"))
      (node (ref "TP7") (pin "1") (pinfunction "TEST_1") (pintype "passive"))
    )
    (net (code "41") (name "Net-(Q6-GND)") (class "Default")
      (node (ref "Q6") (pin "4") (pinfunction "GND_4") (pintype "passive"))
      (node (ref "R61") (pin "1") (pinfunction "1_1") (pintype "passive"))
    )
    (net (code "42") (name "Net-(Q6-IN1+)") (class "Default")
      (node (ref "C16") (pin "2") (pinfunction "2_2") (pintype "passive"))
      (node (ref "D15") (pin "2") (pintype "passive"))
      (node (ref "Q6") (pin "3") (pinfunction "IN1+_3") (pintype "passive"))
      (node (ref "R34") (pin "2") (pinfunction "2_2") (pintype "passive"))
      (node (ref "TP10") (pin "1") (pinfunction "TEST_1") (pintype "passive"))
    )
    (net (code "43") (name "Net-(Q6-IN2+)") (class "Default")
      (node (ref "C15") (pin "2") (pinfunction "2_2") (pintype "passive"))
      (node (ref "D14") (pin "2") (pintype "passive"))
      (node (ref "Q6") (pin "5") (pinfunction "IN2+_5") (pintype "passive"))
      (node (ref "R30") (pin "2") (pinfunction "2_2") (pintype "passive"))
      (node (ref "TP9") (pin "1") (pinfunction "TEST_1") (pintype "passive"))
    )
    (net (code "44") (name "Net-(Q7-GND)") (class "Default")
      (node (ref "Q7") (pin "4") (pinfunction "GND_4") (pintype "passive"))
      (node (ref "R70") (pin "1") (pinfunction "1_1") (pintype "passive"))
    )
    (net (code "45") (name "Net-(Q7-IN1+)") (class "Default")
      (node (ref "C18") (pin "2") (pinfunction "2_2") (pintype "passive"))
      (node (ref "D17") (pin "2") (pintype "passive"))
      (node (ref "Q7") (pin "3") (pinfunction "IN1+_3") (pintype "passive"))
      (node (ref "R39") (pin "2") (pinfunction "2_2") (pintype "passive"))
      (node (ref "R40") (pin "2") (pinfunction "2_2") (pintype "passive"))
      (node (ref "TP12") (pin "1") (pinfunction "TEST_1") (pintype "passive"))
    )
    (net (code "46") (name "Net-(Q7-IN2+)") (class "Default")
      (node (ref "C17") (pin "2") (pinfunction "2_2") (pintype "passive"))
      (node (ref "D16") (pin "2") (pintype "passive"))
      (node (ref "Q7") (pin "5") (pinfunction "IN2+_5") (pintype "passive"))
      (node (ref "R36") (pin "2") (pinfunction "2_2") (pintype "passive"))
      (node (ref "R37") (pin "2") (pinfunction "2_2") (pintype "passive"))
      (node (ref "TP11") (pin "1") (pinfunction "TEST_1") (pintype "passive"))
    )
    (net (code "47") (name "Net-(Q8-GND)") (class "Default")
      (node (ref "Q8") (pin "4") (pinfunction "GND_4") (pintype "passive"))
      (node (ref "R67") (pin "1") (pinfunction "1_1") (pintype "passive"))
    )
    (net (code "48") (name "Net-(Q8-IN1+)") (class "Default")
      (node (ref "C20") (pin "2") (pinfunction "2_2") (pintype "passive"))
      (node (ref "D19") (pin "2") (pintype "passive"))
      (node (ref "Q8") (pin "3") (pinfunction "IN1+_3") (pintype "passive"))
      (node (ref "R43") (pin "2") (pinfunction "2_2") (pintype "passive"))
      (node (ref "TP14") (pin "1") (pinfunction "TEST_1") (pintype "passive"))
    )
    (net (code "49") (name "Net-(Q8-IN2+)") (class "Default")
      (node (ref "C19") (pin "2") (pinfunction "2_2") (pintype "passive"))
      (node (ref "D18") (pin "2") (pintype "passive"))
      (node (ref "Q8") (pin "5") (pinfunction "IN2+_5") (pintype "passive"))
      (node (ref "R42") (pin "2") (pinfunction "2_2") (pintype "passive"))
      (node (ref "TP13") (pin "1") (pinfunction "TEST_1") (pintype "passive"))
    )
    (net (code "50") (name "Net-(Q9-GND)") (class "Default")
      (node (ref "Q9") (pin "4") (pinfunction "GND_4") (pintype "passive"))
      (node (ref "R64") (pin "1") (pinfunction "1_1") (pintype "passive"))
    )
    (net (code "51") (name "Net-(Q9-IN1+)") (class "Default")
      (node (ref "C22") (pin "2") (pinfunction "2_2") (pintype "passive"))
      (node (ref "D21") (pin "2") (pintype "passive"))
      (node (ref "Q9") (pin "3") (pinfunction "IN1+_3") (pintype "passive"))
      (node (ref "R45") (pin "2") (pinfunction "2_2") (pintype "passive"))
      (node (ref "TP16") (pin "1") (pinfunction "TEST_1") (pintype "passive"))
    )
    (net (code "52") (name "Net-(Q9-IN2+)") (class "Default")
      (node (ref "C21") (pin "2") (pinfunction "2_2") (pintype "passive"))
      (node (ref "D20") (pin "2") (pintype "passive"))
      (node (ref "Q9") (pin "5") (pinfunction "IN2+_5") (pintype "passive"))
      (node (ref "R44") (pin "2") (pinfunction "2_2") (pintype "passive"))
      (node (ref "TP15") (pin "1") (pinfunction "TEST_1") (pintype "passive"))
    )
    (net (code "53") (name "PRESSURE") (class "Default")
      (node (ref "Q7") (pin "6") (pinfunction "IN2-_6") (pintype "passive"))
      (node (ref "Q7") (pin "7") (pinfunction "OUT2_7") (pintype "passive"))
    )
    (net (code "54") (name "PRESSURE_IN") (class "Default")
      (node (ref "R37") (pin "1") (pinfunction "1_1") (pintype "passive"))
    )
    (net (code "55") (name "SIGNAL1") (class "Default")
      (node (ref "Q4") (pin "1") (pinfunction "OUT1_1") (pintype "passive"))
      (node (ref "Q4") (pin "2") (pinfunction "IN1-_2") (pintype "passive"))
    )
    (net (code "56") (name "SIGNAL2") (class "Default")
      (node (ref "Q4") (pin "6") (pinfunction "IN2-_6") (pintype "passive"))
      (node (ref "Q4") (pin "7") (pinfunction "OUT2_7") (pintype "passive"))
    )
    (net (code "57") (name "SIGNAL3") (class "Default")
      (node (ref "Q3") (pin "1") (pinfunction "OUT1_1") (pintype "passive"))
      (node (ref "Q3") (pin "2") (pinfunction "IN1-_2") (pintype "passive"))
    )
    (net (code "58") (name "SIGNAL4") (class "Default")
      (node (ref "Q3") (pin "6") (pinfunction "IN2-_6") (pintype "passive"))
      (node (ref "Q3") (pin "7") (pinfunction "OUT2_7") (pintype "passive"))
    )
    (net (code "59") (name "SIGNAL5") (class "Default")
      (node (ref "Q2") (pin "1") (pinfunction "OUT1_1") (pintype "passive"))
      (node (ref "Q2") (pin "2") (pinfunction "IN1-_2") (pintype "passive"))
    )
    (net (code "60") (name "SIGNAL6") (class "Default")
      (node (ref "Q2") (pin "6") (pinfunction "IN2-_6") (pintype "passive"))
      (node (ref "Q2") (pin "7") (pinfunction "OUT2_7") (pintype "passive"))
    )
    (net (code "61") (name "SIGNAL_1") (class "Default")
      (node (ref "R23") (pin "1") (pinfunction "1_1") (pintype "passive"))
      (node (ref "R24") (pin "1") (pinfunction "1_1") (pintype "passive"))
    )
    (net (code "62") (name "SIGNAL_2") (class "Default")
      (node (ref "R20") (pin "1") (pinfunction "1_1") (pintype "passive"))
      (node (ref "R21") (pin "1") (pinfunction "1_1") (pintype "passive"))
    )
    (net (code "63") (name "SIGNAL_3") (class "Default")
      (node (ref "R17") (pin "1") (pinfunction "1_1") (pintype "passive"))
      (node (ref "R18") (pin "1") (pinfunction "1_1") (pintype "passive"))
    )
    (net (code "64") (name "SIGNAL_4") (class "Default")
      (node (ref "R14") (pin "1") (pinfunction "1_1") (pintype "passive"))
      (node (ref "R15") (pin "1") (pinfunction "1_1") (pintype "passive"))
    )
    (net (code "65") (name "SIGNAL_5") (class "Default")
      (node (ref "R11") (pin "1") (pinfunction "1_1") (pintype "passive"))
      (node (ref "R12") (pin "1") (pinfunction "1_1") (pintype "passive"))
    )
    (net (code "66") (name "SIGNAL_6") (class "Default")
      (node (ref "R8") (pin "1") (pinfunction "1_1") (pintype "passive"))
      (node (ref "R9") (pin "1") (pinfunction "1_1") (pintype "passive"))
    )
    (net (code "67") (name "THERM1") (class "Default")
      (node (ref "Q6") (pin "1") (pinfunction "OUT1_1") (pintype "passive"))
      (node (ref "Q6") (pin "2") (pinfunction "IN1-_2") (pintype "passive"))
    )
    (net (code "68") (name "THERM2") (class "Default")
      (node (ref "Q6") (pin "6") (pinfunction "IN2-_6") (pintype "passive"))
      (node (ref "Q6") (pin "7") (pinfunction "OUT2_7") (pintype "passive"))
    )
    (net (code "69") (name "THERM3") (class "Default")
      (node (ref "Q5") (pin "1") (pinfunction "OUT1_1") (pintype "passive"))
      (node (ref "Q5") (pin "2") (pinfunction "IN1-_2") (pintype "passive"))
    )
    (net (code "70") (name "THERM4") (class "Default")
      (node (ref "Q5") (pin "6") (pinfunction "IN2-_6") (pintype "passive"))
      (node (ref "Q5") (pin "7") (pinfunction "OUT2_7") (pintype "passive"))
    )
    (net (code "71") (name "THERM_1") (class "Default")
      (node (ref "R32") (pin "1") (pinfunction "1_1") (pintype "passive"))
      (node (ref "R34") (pin "1") (pinfunction "1_1") (pintype "passive"))
    )
    (net (code "72") (name "THERM_2") (class "Default")
      (node (ref "R29") (pin "1") (pinfunction "1_1") (pintype "passive"))
      (node (ref "R30") (pin "1") (pinfunction "1_1") (pintype "passive"))
    )
    (net (code "73") (name "THERM_3") (class "Default")
      (node (ref "R27") (pin "1") (pinfunction "1_1") (pintype "passive"))
      (node (ref "R28") (pin "1") (pinfunction "1_1") (pintype "passive"))
    )
    (net (code "74") (name "THERM_4") (class "Default")
      (node (ref "R25") (pin "1") (pinfunction "1_1") (pintype "passive"))
      (node (ref "R26") (pin "1") (pinfunction "1_1") (pintype "passive"))
    )
  )
)
